# design.net
KiCad netlist of a schematic drawn in Altium Designer
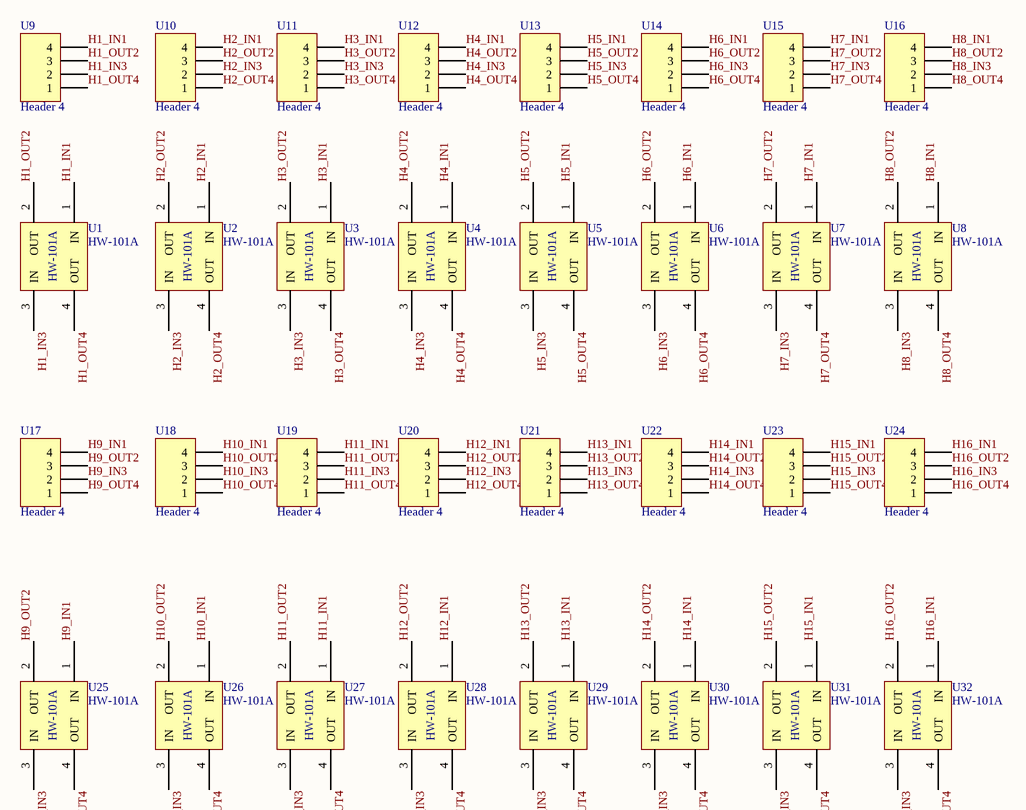
[diagram p0: 检测板.SchDoc]

(export (version "E")
  (design (tool "Eeschema 10.0.6"))
  (components
    (comp (ref "U1") (value "HW-101A") (footprint "SOT-23-4") (libsource (lib "磁导航") (part "HW-101A")))
    (comp (ref "U2") (value "HW-101A") (footprint "SOT-23-4") (libsource (lib "磁导航") (part "HW-101A")))
    (comp (ref "U3") (value "HW-101A") (footprint "SOT-23-4") (libsource (lib "磁导航") (part "HW-101A")))
    (comp (ref "U4") (value "HW-101A") (footprint "SOT-23-4") (libsource (lib "磁导航") (part "HW-101A")))
    (comp (ref "U5") (value "HW-101A") (footprint "SOT-23-4") (libsource (lib "磁导航") (part "HW-101A")))
    (comp (ref "U6") (value "HW-101A") (footprint "SOT-23-4") (libsource (lib "磁导航") (part "HW-101A")))
    (comp (ref "U7") (value "HW-101A") (footprint "SOT-23-4") (libsource (lib "磁导航") (part "HW-101A")))
    (comp (ref "U8") (value "HW-101A") (footprint "SOT-23-4") (libsource (lib "磁导航") (part "HW-101A")))
    (comp (ref "U9")
      (value "Header 4")
      (footprint "PIN4")
      (description "Header, 4-Pin")
      (fields (field (name "PUBLISHER") "Altium Limited"))
      (libsource (lib "Miscellaneous Connectors") (part "Header 4"))
    )
    (comp (ref "U10")
      (value "Header 4")
      (footprint "PIN4")
      (description "Header, 4-Pin")
      (fields (field (name "PUBLISHER") "Altium Limited"))
      (libsource (lib "Miscellaneous Connectors") (part "Header 4"))
    )
    (comp (ref "U11")
      (value "Header 4")
      (footprint "PIN4")
      (description "Header, 4-Pin")
      (fields (field (name "PUBLISHER") "Altium Limited"))
      (libsource (lib "Miscellaneous Connectors") (part "Header 4"))
    )
    (comp (ref "U12")
      (value "Header 4")
      (footprint "PIN4")
      (description "Header, 4-Pin")
      (fields (field (name "PUBLISHER") "Altium Limited"))
      (libsource (lib "Miscellaneous Connectors") (part "Header 4"))
    )
    (comp (ref "U13")
      (value "Header 4")
      (footprint "PIN4")
      (description "Header, 4-Pin")
      (fields (field (name "PUBLISHER") "Altium Limited"))
      (libsource (lib "Miscellaneous Connectors") (part "Header 4"))
    )
    (comp (ref "U14")
      (value "Header 4")
      (footprint "PIN4")
      (description "Header, 4-Pin")
      (fields (field (name "PUBLISHER") "Altium Limited"))
      (libsource (lib "Miscellaneous Connectors") (part "Header 4"))
    )
    (comp (ref "U15")
      (value "Header 4")
      (footprint "PIN4")
      (description "Header, 4-Pin")
      (fields (field (name "PUBLISHER") "Altium Limited"))
      (libsource (lib "Miscellaneous Connectors") (part "Header 4"))
    )
    (comp (ref "U16")
      (value "Header 4")
      (footprint "PIN4")
      (description "Header, 4-Pin")
      (fields (field (name "PUBLISHER") "Altium Limited"))
      (libsource (lib "Miscellaneous Connectors") (part "Header 4"))
    )
    (comp (ref "U17")
      (value "Header 4")
      (footprint "PIN4")
      (description "Header, 4-Pin")
      (fields (field (name "PUBLISHER") "Altium Limited"))
      (libsource (lib "Miscellaneous Connectors") (part "Header 4"))
    )
    (comp (ref "U18")
      (value "Header 4")
      (footprint "PIN4")
      (description "Header, 4-Pin")
      (fields (field (name "PUBLISHER") "Altium Limited"))
      (libsource (lib "Miscellaneous Connectors") (part "Header 4"))
    )
    (comp (ref "U19")
      (value "Header 4")
      (footprint "PIN4")
      (description "Header, 4-Pin")
      (fields (field (name "PUBLISHER") "Altium Limited"))
      (libsource (lib "Miscellaneous Connectors") (part "Header 4"))
    )
    (comp (ref "U20")
      (value "Header 4")
      (footprint "PIN4")
      (description "Header, 4-Pin")
      (fields (field (name "PUBLISHER") "Altium Limited"))
      (libsource (lib "Miscellaneous Connectors") (part "Header 4"))
    )
    (comp (ref "U21")
      (value "Header 4")
      (footprint "PIN4")
      (description "Header, 4-Pin")
      (fields (field (name "PUBLISHER") "Altium Limited"))
      (libsource (lib "Miscellaneous Connectors") (part "Header 4"))
    )
    (comp (ref "U22")
      (value "Header 4")
      (footprint "PIN4")
      (description "Header, 4-Pin")
      (fields (field (name "PUBLISHER") "Altium Limited"))
      (libsource (lib "Miscellaneous Connectors") (part "Header 4"))
    )
    (comp (ref "U23")
      (value "Header 4")
      (footprint "PIN4")
      (description "Header, 4-Pin")
      (fields (field (name "PUBLISHER") "Altium Limited"))
      (libsource (lib "Miscellaneous Connectors") (part "Header 4"))
    )
    (comp (ref "U24")
      (value "Header 4")
      (footprint "PIN4")
      (description "Header, 4-Pin")
      (fields (field (name "PUBLISHER") "Altium Limited"))
      (libsource (lib "Miscellaneous Connectors") (part "Header 4"))
    )
    (comp (ref "U25") (value "HW-101A") (footprint "SOT-23-4") (libsource (lib "磁导航") (part "HW-101A")))
    (comp (ref "U26") (value "HW-101A") (footprint "SOT-23-4") (libsource (lib "磁导航") (part "HW-101A")))
    (comp (ref "U27") (value "HW-101A") (footprint "SOT-23-4") (libsource (lib "磁导航") (part "HW-101A")))
    (comp (ref "U28") (value "HW-101A") (footprint "SOT-23-4") (libsource (lib "磁导航") (part "HW-101A")))
    (comp (ref "U29") (value "HW-101A") (footprint "SOT-23-4") (libsource (lib "磁导航") (part "HW-101A")))
    (comp (ref "U30") (value "HW-101A") (footprint "SOT-23-4") (libsource (lib "磁导航") (part "HW-101A")))
    (comp (ref "U31") (value "HW-101A") (footprint "SOT-23-4") (libsource (lib "磁导航") (part "HW-101A")))
    (comp (ref "U32") (value "HW-101A") (footprint "SOT-23-4") (libsource (lib "磁导航") (part "HW-101A")))
  )
  (nets
    (net (code "1") (name "/H1_IN1") (class "Default")
      (node (ref "U1") (pin "1") (pinfunction "IN_1") (pintype "passive"))
      (node (ref "U9") (pin "4") (pinfunction "4_4") (pintype "passive"))
    )
    (net (code "2") (name "/H1_IN3") (class "Default")
      (node (ref "U1") (pin "3") (pinfunction "IN_3") (pintype "passive"))
      (node (ref "U9") (pin "2") (pinfunction "2_2") (pintype "passive"))
    )
    (net (code "3") (name "/H1_OUT2") (class "Default")
      (node (ref "U1") (pin "2") (pinfunction "OUT_2") (pintype "passive"))
      (node (ref "U9") (pin "3") (pinfunction "3_3") (pintype "passive"))
    )
    (net (code "4") (name "/H1_OUT4") (class "Default")
      (node (ref "U1") (pin "4") (pinfunction "OUT_4") (pintype "passive"))
      (node (ref "U9") (pin "1") (pinfunction "1_1") (pintype "passive"))
    )
    (net (code "5") (name "/H2_IN1") (class "Default")
      (node (ref "U10") (pin "4") (pinfunction "4_4") (pintype "passive"))
      (node (ref "U2") (pin "1") (pinfunction "IN_1") (pintype "passive"))
    )
    (net (code "6") (name "/H2_IN3") (class "Default")
      (node (ref "U10") (pin "2") (pinfunction "2_2") (pintype "passive"))
      (node (ref "U2") (pin "3") (pinfunction "IN_3") (pintype "passive"))
    )
    (net (code "7") (name "/H2_OUT2") (class "Default")
      (node (ref "U10") (pin "3") (pinfunction "3_3") (pintype "passive"))
      (node (ref "U2") (pin "2") (pinfunction "OUT_2") (pintype "passive"))
    )
    (net (code "8") (name "/H2_OUT4") (class "Default")
      (node (ref "U10") (pin "1") (pinfunction "1_1") (pintype "passive"))
      (node (ref "U2") (pin "4") (pinfunction "OUT_4") (pintype "passive"))
    )
    (net (code "9") (name "/H3_IN1") (class "Default")
      (node (ref "U11") (pin "4") (pinfunction "4_4") (pintype "passive"))
      (node (ref "U3") (pin "1") (pinfunction "IN_1") (pintype "passive"))
    )
    (net (code "10") (name "/H3_IN3") (class "Default")
      (node (ref "U11") (pin "2") (pinfunction "2_2") (pintype "passive"))
      (node (ref "U3") (pin "3") (pinfunction "IN_3") (pintype "passive"))
    )
    (net (code "11") (name "/H3_OUT2") (class "Default")
      (node (ref "U11") (pin "3") (pinfunction "3_3") (pintype "passive"))
      (node (ref "U3") (pin "2") (pinfunction "OUT_2") (pintype "passive"))
    )
    (net (code "12") (name "/H3_OUT4") (class "Default")
      (node (ref "U11") (pin "1") (pinfunction "1_1") (pintype "passive"))
      (node (ref "U3") (pin "4") (pinfunction "OUT_4") (pintype "passive"))
    )
    (net (code "13") (name "/H4_IN1") (class "Default")
      (node (ref "U12") (pin "4") (pinfunction "4_4") (pintype "passive"))
      (node (ref "U4") (pin "1") (pinfunction "IN_1") (pintype "passive"))
    )
    (net (code "14") (name "/H4_IN3") (class "Default")
      (node (ref "U12") (pin "2") (pinfunction "2_2") (pintype "passive"))
      (node (ref "U4") (pin "3") (pinfunction "IN_3") (pintype "passive"))
    )
    (net (code "15") (name "/H4_OUT2") (class "Default")
      (node (ref "U12") (pin "3") (pinfunction "3_3") (pintype "passive"))
      (node (ref "U4") (pin "2") (pinfunction "OUT_2") (pintype "passive"))
    )
    (net (code "16") (name "/H4_OUT4") (class "Default")
      (node (ref "U12") (pin "1") (pinfunction "1_1") (pintype "passive"))
      (node (ref "U4") (pin "4") (pinfunction "OUT_4") (pintype "passive"))
    )
    (net (code "17") (name "/H5_IN1") (class "Default")
      (node (ref "U13") (pin "4") (pinfunction "4_4") (pintype "passive"))
      (node (ref "U5") (pin "1") (pinfunction "IN_1") (pintype "passive"))
    )
    (net (code "18") (name "/H5_IN3") (class "Default")
      (node (ref "U13") (pin "2") (pinfunction "2_2") (pintype "passive"))
      (node (ref "U5") (pin "3") (pinfunction "IN_3") (pintype "passive"))
    )
    (net (code "19") (name "/H5_OUT2") (class "Default")
      (node (ref "U13") (pin "3") (pinfunction "3_3") (pintype "passive"))
      (node (ref "U5") (pin "2") (pinfunction "OUT_2") (pintype "passive"))
    )
    (net (code "20") (name "/H5_OUT4") (class "Default")
      (node (ref "U13") (pin "1") (pinfunction "1_1") (pintype "passive"))
      (node (ref "U5") (pin "4") (pinfunction "OUT_4") (pintype "passive"))
    )
    (net (code "21") (name "/H6_IN1") (class "Default")
      (node (ref "U14") (pin "4") (pinfunction "4_4") (pintype "passive"))
      (node (ref "U6") (pin "1") (pinfunction "IN_1") (pintype "passive"))
    )
    (net (code "22") (name "/H6_IN3") (class "Default")
      (node (ref "U14") (pin "2") (pinfunction "2_2") (pintype "passive"))
      (node (ref "U6") (pin "3") (pinfunction "IN_3") (pintype "passive"))
    )
    (net (code "23") (name "/H6_OUT2") (class "Default")
      (node (ref "U14") (pin "3") (pinfunction "3_3") (pintype "passive"))
      (node (ref "U6") (pin "2") (pinfunction "OUT_2") (pintype "passive"))
    )
    (net (code "24") (name "/H6_OUT4") (class "Default")
      (node (ref "U14") (pin "1") (pinfunction "1_1") (pintype "passive"))
      (node (ref "U6") (pin "4") (pinfunction "OUT_4") (pintype "passive"))
    )
    (net (code "25") (name "/H7_IN1") (class "Default")
      (node (ref "U15") (pin "4") (pinfunction "4_4") (pintype "passive"))
      (node (ref "U7") (pin "1") (pinfunction "IN_1") (pintype "passive"))
    )
    (net (code "26") (name "/H7_IN3") (class "Default")
      (node (ref "U15") (pin "2") (pinfunction "2_2") (pintype "passive"))
      (node (ref "U7") (pin "3") (pinfunction "IN_3") (pintype "passive"))
    )
    (net (code "27") (name "/H7_OUT2") (class "Default")
      (node (ref "U15") (pin "3") (pinfunction "3_3") (pintype "passive"))
      (node (ref "U7") (pin "2") (pinfunction "OUT_2") (pintype "passive"))
    )
    (net (code "28") (name "/H7_OUT4") (class "Default")
      (node (ref "U15") (pin "1") (pinfunction "1_1") (pintype "passive"))
      (node (ref "U7") (pin "4") (pinfunction "OUT_4") (pintype "passive"))
    )
    (net (code "29") (name "/H8_IN1") (class "Default")
      (node (ref "U16") (pin "4") (pinfunction "4_4") (pintype "passive"))
      (node (ref "U8") (pin "1") (pinfunction "IN_1") (pintype "passive"))
    )
    (net (code "30") (name "/H8_IN3") (class "Default")
      (node (ref "U16") (pin "2") (pinfunction "2_2") (pintype "passive"))
      (node (ref "U8") (pin "3") (pinfunction "IN_3") (pintype "passive"))
    )
    (net (code "31") (name "/H8_OUT2") (class "Default")
      (node (ref "U16") (pin "3") (pinfunction "3_3") (pintype "passive"))
      (node (ref "U8") (pin "2") (pinfunction "OUT_2") (pintype "passive"))
    )
    (net (code "32") (name "/H8_OUT4") (class "Default")
      (node (ref "U16") (pin "1") (pinfunction "1_1") (pintype "passive"))
      (node (ref "U8") (pin "4") (pinfunction "OUT_4") (pintype "passive"))
    )
    (net (code "33") (name "/H9_IN1") (class "Default")
      (node (ref "U17") (pin "4") (pinfunction "4_4") (pintype "passive"))
      (node (ref "U25") (pin "1") (pinfunction "IN_1") (pintype "passive"))
    )
    (net (code "34") (name "/H9_IN3") (class "Default")
      (node (ref "U17") (pin "2") (pinfunction "2_2") (pintype "passive"))
      (node (ref "U25") (pin "3") (pinfunction "IN_3") (pintype "passive"))
    )
    (net (code "35") (name "/H9_OUT2") (class "Default")
      (node (ref "U17") (pin "3") (pinfunction "3_3") (pintype "passive"))
      (node (ref "U25") (pin "2") (pinfunction "OUT_2") (pintype "passive"))
    )
    (net (code "36") (name "/H9_OUT4") (class "Default")
      (node (ref "U17") (pin "1") (pinfunction "1_1") (pintype "passive"))
      (node (ref "U25") (pin "4") (pinfunction "OUT_4") (pintype "passive"))
    )
    (net (code "37") (name "/H10_IN1") (class "Default")
      (node (ref "U18") (pin "4") (pinfunction "4_4") (pintype "passive"))
      (node (ref "U26") (pin "1") (pinfunction "IN_1") (pintype "passive"))
    )
    (net (code "38") (name "/H10_IN3") (class "Default")
      (node (ref "U18") (pin "2") (pinfunction "2_2") (pintype "passive"))
      (node (ref "U26") (pin "3") (pinfunction "IN_3") (pintype "passive"))
    )
    (net (code "39") (name "/H10_OUT2") (class "Default")
      (node (ref "U18") (pin "3") (pinfunction "3_3") (pintype "passive"))
      (node (ref "U26") (pin "2") (pinfunction "OUT_2") (pintype "passive"))
    )
    (net (code "40") (name "/H10_OUT4") (class "Default")
      (node (ref "U18") (pin "1") (pinfunction "1_1") (pintype "passive"))
      (node (ref "U26") (pin "4") (pinfunction "OUT_4") (pintype "passive"))
    )
    (net (code "41") (name "/H11_IN1") (class "Default")
      (node (ref "U19") (pin "4") (pinfunction "4_4") (pintype "passive"))
      (node (ref "U27") (pin "1") (pinfunction "IN_1") (pintype "passive"))
    )
    (net (code "42") (name "/H11_IN3") (class "Default")
      (node (ref "U19") (pin "2") (pinfunction "2_2") (pintype "passive"))
      (node (ref "U27") (pin "3") (pinfunction "IN_3") (pintype "passive"))
    )
    (net (code "43") (name "/H11_OUT2") (class "Default")
      (node (ref "U19") (pin "3") (pinfunction "3_3") (pintype "passive"))
      (node (ref "U27") (pin "2") (pinfunction "OUT_2") (pintype "passive"))
    )
    (net (code "44") (name "/H11_OUT4") (class "Default")
      (node (ref "U19") (pin "1") (pinfunction "1_1") (pintype "passive"))
      (node (ref "U27") (pin "4") (pinfunction "OUT_4") (pintype "passive"))
    )
    (net (code "45") (name "/H12_IN1") (class "Default")
      (node (ref "U20") (pin "4") (pinfunction "4_4") (pintype "passive"))
      (node (ref "U28") (pin "1") (pinfunction "IN_1") (pintype "passive"))
    )
    (net (code "46") (name "/H12_IN3") (class "Default")
      (node (ref "U20") (pin "2") (pinfunction "2_2") (pintype "passive"))
      (node (ref "U28") (pin "3") (pinfunction "IN_3") (pintype "passive"))
    )
    (net (code "47") (name "/H12_OUT2") (class "Default")
      (node (ref "U20") (pin "3") (pinfunction "3_3") (pintype "passive"))
      (node (ref "U28") (pin "2") (pinfunction "OUT_2") (pintype "passive"))
    )
    (net (code "48") (name "/H12_OUT4") (class "Default")
      (node (ref "U20") (pin "1") (pinfunction "1_1") (pintype "passive"))
      (node (ref "U28") (pin "4") (pinfunction "OUT_4") (pintype "passive"))
    )
    (net (code "49") (name "/H13_IN1") (class "Default")
      (node (ref "U21") (pin "4") (pinfunction "4_4") (pintype "passive"))
      (node (ref "U29") (pin "1") (pinfunction "IN_1") (pintype "passive"))
    )
    (net (code "50") (name "/H13_IN3") (class "Default")
      (node (ref "U21") (pin "2") (pinfunction "2_2") (pintype "passive"))
      (node (ref "U29") (pin "3") (pinfunction "IN_3") (pintype "passive"))
    )
    (net (code "51") (name "/H13_OUT2") (class "Default")
      (node (ref "U21") (pin "3") (pinfunction "3_3") (pintype "passive"))
      (node (ref "U29") (pin "2") (pinfunction "OUT_2") (pintype "passive"))
    )
    (net (code "52") (name "/H13_OUT4") (class "Default")
      (node (ref "U21") (pin "1") (pinfunction "1_1") (pintype "passive"))
      (node (ref "U29") (pin "4") (pinfunction "OUT_4") (pintype "passive"))
    )
    (net (code "53") (name "/H14_IN1") (class "Default")
      (node (ref "U22") (pin "4") (pinfunction "4_4") (pintype "passive"))
      (node (ref "U30") (pin "1") (pinfunction "IN_1") (pintype "passive"))
    )
    (net (code "54") (name "/H14_IN3") (class "Default")
      (node (ref "U22") (pin "2") (pinfunction "2_2") (pintype "passive"))
      (node (ref "U30") (pin "3") (pinfunction "IN_3") (pintype "passive"))
    )
    (net (code "55") (name "/H14_OUT2") (class "Default")
      (node (ref "U22") (pin "3") (pinfunction "3_3") (pintype "passive"))
      (node (ref "U30") (pin "2") (pinfunction "OUT_2") (pintype "passive"))
    )
    (net (code "56") (name "/H14_OUT4") (class "Default")
      (node (ref "U22") (pin "1") (pinfunction "1_1") (pintype "passive"))
      (node (ref "U30") (pin "4") (pinfunction "OUT_4") (pintype "passive"))
    )
    (net (code "57") (name "/H15_IN1") (class "Default")
      (node (ref "U23") (pin "4") (pinfunction "4_4") (pintype "passive"))
      (node (ref "U31") (pin "1") (pinfunction "IN_1") (pintype "passive"))
    )
    (net (code "58") (name "/H15_IN3") (class "Default")
      (node (ref "U23") (pin "2") (pinfunction "2_2") (pintype "passive"))
      (node (ref "U31") (pin "3") (pinfunction "IN_3") (pintype "passive"))
    )
    (net (code "59") (name "/H15_OUT2") (class "Default")
      (node (ref "U23") (pin "3") (pinfunction "3_3") (pintype "passive"))
      (node (ref "U31") (pin "2") (pinfunction "OUT_2") (pintype "passive"))
    )
    (net (code "60") (name "/H15_OUT4") (class "Default")
      (node (ref "U23") (pin "1") (pinfunction "1_1") (pintype "passive"))
      (node (ref "U31") (pin "4") (pinfunction "OUT_4") (pintype "passive"))
    )
    (net (code "61") (name "/H16_IN1") (class "Default")
      (node (ref "U24") (pin "4") (pinfunction "4_4") (pintype "passive"))
      (node (ref "U32") (pin "1") (pinfunction "IN_1") (pintype "passive"))
    )
    (net (code "62") (name "/H16_IN3") (class "Default")
      (node (ref "U24") (pin "2") (pinfunction "2_2") (pintype "passive"))
      (node (ref "U32") (pin "3") (pinfunction "IN_3") (pintype "passive"))
    )
    (net (code "63") (name "/H16_OUT2") (class "Default")
      (node (ref "U24") (pin "3") (pinfunction "3_3") (pintype "passive"))
      (node (ref "U32") (pin "2") (pinfunction "OUT_2") (pintype "passive"))
    )
    (net (code "64") (name "/H16_OUT4") (class "Default")
      (node (ref "U24") (pin "1") (pinfunction "1_1") (pintype "passive"))
      (node (ref "U32") (pin "4") (pinfunction "OUT_4") (pintype "passive"))
    )
  )
)
